# Real_Time_Clock.net
KiCad netlist of a schematic drawn in Altium Designer
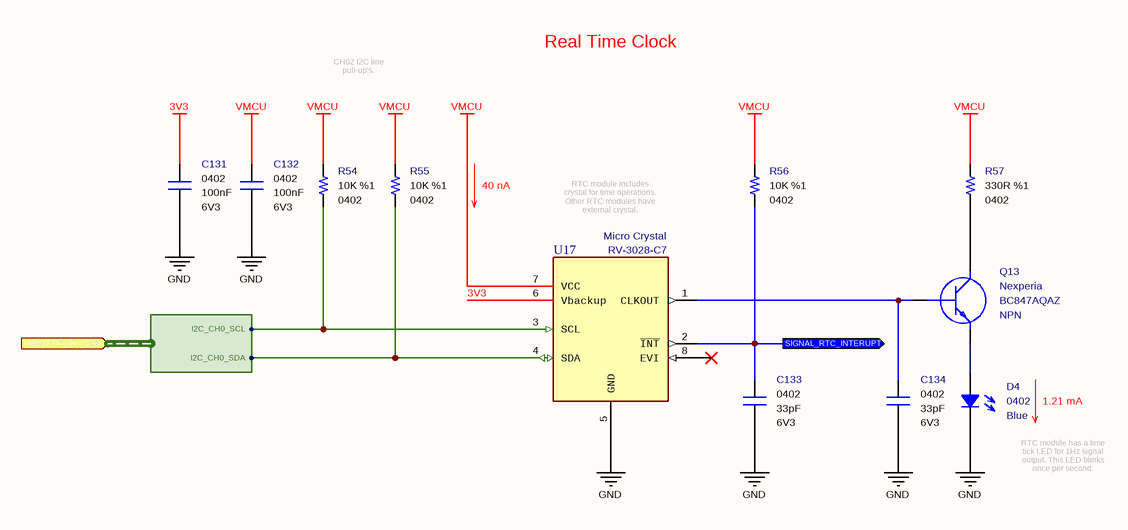
[diagram p0: Real Time Clock.SchDoc]

(export (version "E")
  (design (tool "Eeschema 10.0.6"))
  (components
    (comp (ref "C131")
      (value "100nF")
      (footprint "CAPACITOR_0402")
      (description "Capacitor - 100nF [0402-6V3] (Ceramic)")
      (fields
        (field (name "TOLERANCE") "%10")
        (field (name "CASE") "0402")
        (field (name "VOLTAGE") "6V3")
        (field (name "MANUFACTURER PART NUMBER") "04026D104KAT4A")
      )
      (libsource (lib "Ovoo_Library") (part "Capacitor - 100nF [0402-6V3]"))
    )
    (comp (ref "C132")
      (value "100nF")
      (footprint "CAPACITOR_0402")
      (description "Capacitor - 100nF [0402-6V3] (Ceramic)")
      (fields
        (field (name "TOLERANCE") "%10")
        (field (name "CASE") "0402")
        (field (name "VOLTAGE") "6V3")
        (field (name "MANUFACTURER PART NUMBER") "04026D104KAT4A")
      )
      (libsource (lib "Ovoo_Library") (part "Capacitor - 100nF [0402-6V3]"))
    )
    (comp (ref "C133")
      (value "33pF")
      (footprint "CAPACITOR_0402")
      (description "Capacitor - 33pF [0402] (Ceramic)")
      (fields
        (field (name "CASE") "0402")
        (field (name "TOLERANCE") "10%")
        (field (name "VOLTAGE") "6V3")
        (field (name "MANUFACTURER PART NUMBER") "C0402C330J9RACAUTO")
      )
      (libsource (lib "Ovoo_Library") (part "Capacitor - 33pF [0402-6V3]"))
    )
    (comp (ref "C134")
      (value "33pF")
      (footprint "CAPACITOR_0402")
      (description "Capacitor - 33pF [0402] (Ceramic)")
      (fields
        (field (name "CASE") "0402")
        (field (name "TOLERANCE") "10%")
        (field (name "VOLTAGE") "6V3")
        (field (name "MANUFACTURER PART NUMBER") "C0402C330J9RACAUTO")
      )
      (libsource (lib "Ovoo_Library") (part "Capacitor - 33pF [0402-6V3]"))
    )
    (comp (ref "D4")
      (value "SMD LED (Blue)")
      (footprint "LED_0402")
      (description "Standard LEDs - SMD PICOLEDTM;BLUE LED; 25M @ 5MA")
      (fields
        (field (name "CASE") "0402")
        (field (name "COLOR") "Blue")
        (field (name "MANUFACTURER PART NUMBER") "SMLP13BC8TT86")
        (field (name "MOUSER PART NUMBER") "755-SMLP13BC8TT86")
      )
      (libsource (lib "Ovoo_Library") (part "Diode - LED (0402-Blue)"))
    )
    (comp (ref "Q13")
      (value "BC847AQAZ")
      (footprint "SOT1215")
      (description "Bipolar NPN Transistors")
      (fields
        (field (name "POLARITY") "NPN")
        (field (name "MANUFACTURER NAME") "Nexperia")
        (field (name "MANUFACTURER PART NUMBER") "BC847AQAZ")
      )
      (libsource (lib "Ovoo_Library") (part "Transistor - BC847"))
    )
    (comp (ref "R54")
      (value "10K")
      (footprint "RESISTOR_0402")
      (description "Thick Film Resistors - SMD 1/16 W 10 Kohms 1%")
      (fields
        (field (name "TOLERANCE") "%1")
        (field (name "CASE") "0402")
        (field (name "MANUFACTURER PART NUMBER") "CRCW040210K0FKED")
        (field (name "MOUSER PART NUMBER") "71-CRCW0402-10K-E3")
      )
      (libsource (lib "Ovoo_Library") (part "Resistor - 10K"))
    )
    (comp (ref "R55")
      (value "10K")
      (footprint "RESISTOR_0402")
      (description "Thick Film Resistors - SMD 1/16 W 10 Kohms 1%")
      (fields
        (field (name "TOLERANCE") "%1")
        (field (name "CASE") "0402")
        (field (name "MANUFACTURER PART NUMBER") "CRCW040210K0FKED")
        (field (name "MOUSER PART NUMBER") "71-CRCW0402-10K-E3")
      )
      (libsource (lib "Ovoo_Library") (part "Resistor - 10K"))
    )
    (comp (ref "R56")
      (value "10K")
      (footprint "RESISTOR_0402")
      (description "Thick Film Resistors - SMD 1/16 W 10 Kohms 1%")
      (fields
        (field (name "TOLERANCE") "%1")
        (field (name "CASE") "0402")
        (field (name "MANUFACTURER PART NUMBER") "CRCW040210K0FKED")
        (field (name "MOUSER PART NUMBER") "71-CRCW0402-10K-E3")
      )
      (libsource (lib "Ovoo_Library") (part "Resistor - 10K"))
    )
    (comp (ref "R57")
      (value "330R")
      (footprint "RESISTOR_0402")
      (description "Thick Film Resistors - SMD 1/16 W 330 Ohm 1%")
      (fields
        (field (name "TOLERANCE") "%1")
        (field (name "CASE") "0402")
        (field (name "MANUFACTURER PART NUMBER") "CRCW0402330RFKED")
        (field (name "MOUSER PART NUMBER") "71-CRCW0402-330-E3")
      )
      (libsource (lib "Ovoo_Library") (part "Resistor - 330R"))
    )
    (comp (ref "U17")
      (value "Real Time Clock")
      (footprint "RV-3028-C7")
      (description "Real Time Clock 32.768kHz I2C Time Acc. 1ppm")
      (fields
        (field (name "MOUSER PART NUMBER") "428-203591-MG01")
        (field (name "MANUFACTURER PART NUMBER") "RV-3028-C7")
        (field (name "MANUFACTURER NAME") "Micro Crystal")
      )
      (libsource (lib "Ovoo_Library") (part "IC - RV-3028-C7"))
    )
  )
  (nets
    (net (code "2") (name "/SIGNAL_RTC_INTERUPT") (class "Default")
      (node (ref "C133") (pin "1") (pinfunction "1_1") (pintype "passive"))
      (node (ref "R56") (pin "1") (pinfunction "1_1") (pintype "passive"))
      (node (ref "U17") (pin "2") (pinfunction "~{INT}_2") (pintype "output"))
    )
    (net (code "4") (name "3V3") (class "Default")
      (node (ref "C131") (pin "2") (pinfunction "2_2") (pintype "passive"))
      (node (ref "U17") (pin "6") (pinfunction "Vbackup_6") (pintype "power_in"))
    )
    (net (code "5") (name "GND") (class "Default")
      (node (ref "C131") (pin "1") (pinfunction "1_1") (pintype "passive"))
      (node (ref "C132") (pin "1") (pinfunction "1_1") (pintype "passive"))
      (node (ref "C133") (pin "2") (pinfunction "2_2") (pintype "passive"))
      (node (ref "C134") (pin "2") (pinfunction "2_2") (pintype "passive"))
      (node (ref "D4") (pin "1") (pinfunction "1_1") (pintype "passive"))
      (node (ref "U17") (pin "5") (pinfunction "GND_5") (pintype "power_in"))
    )
    (net (code "6") (name "Net-(Q13-B)") (class "Default")
      (node (ref "C134") (pin "1") (pinfunction "1_1") (pintype "passive"))
      (node (ref "Q13") (pin "1") (pinfunction "B_1") (pintype "passive"))
      (node (ref "U17") (pin "1") (pinfunction "CLKOUT_1") (pintype "output"))
    )
    (net (code "7") (name "Net-(Q13-C)") (class "Default")
      (node (ref "Q13") (pin "3") (pinfunction "C_3") (pintype "passive"))
      (node (ref "R57") (pin "1") (pinfunction "1_1") (pintype "passive"))
    )
    (net (code "8") (name "Net-(Q13-E)") (class "Default")
      (node (ref "D4") (pin "2") (pinfunction "2_2") (pintype "passive"))
      (node (ref "Q13") (pin "2") (pinfunction "E_2") (pintype "passive"))
    )
    (net (code "9") (name "Net-(U17-SCL)") (class "Default")
      (node (ref "R54") (pin "1") (pinfunction "1_1") (pintype "passive"))
      (node (ref "U17") (pin "3") (pinfunction "SCL_3") (pintype "input"))
    )
    (net (code "10") (name "Net-(U17-SDA)") (class "Default")
      (node (ref "R55") (pin "1") (pinfunction "1_1") (pintype "passive"))
      (node (ref "U17") (pin "4") (pinfunction "SDA_4") (pintype "bidirectional"))
    )
    (net (code "11") (name "VMCU") (class "Default")
      (node (ref "C132") (pin "2") (pinfunction "2_2") (pintype "passive"))
      (node (ref "R54") (pin "2") (pinfunction "2_2") (pintype "passive"))
      (node (ref "R55") (pin "2") (pinfunction "2_2") (pintype "passive"))
      (node (ref "R56") (pin "2") (pinfunction "2_2") (pintype "passive"))
      (node (ref "R57") (pin "2") (pinfunction "2_2") (pintype "passive"))
      (node (ref "U17") (pin "7") (pinfunction "VCC_7") (pintype "power_in"))
    )
    (net (code "12") (name "unconnected-(U17-EVI-Pad8)") (class "Default")
      (node (ref "U17") (pin "8") (pinfunction "EVI_8") (pintype "input+no_connect"))
    )
  )
)
